# Sensor_shoot.net
KiCad netlist of a schematic drawn in Altium Designer
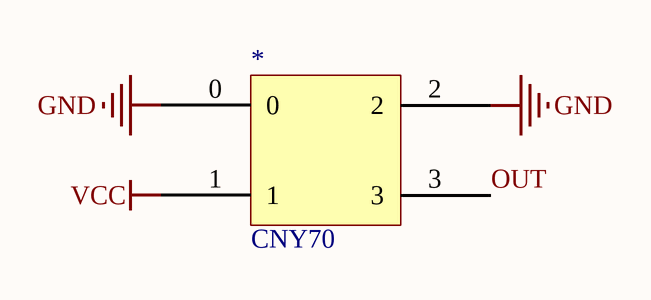
[diagram p0: Sensor shoot.SchDoc]

(export (version "E")
  (design (tool "Eeschema 10.0.6"))
  (components (comp (ref "*") (value "CNY70") (footprint "CNY70") (libsource (lib "KN2CLib") (part "CNY70"))))
  (nets
    (net (code "1") (name "/OUT") (class "Default")
      (node (ref "*") (pin "3") (pinfunction "3_3") (pintype "passive"))
    )
    (net (code "2") (name "GND") (class "Default")
      (node (ref "*") (pin "0") (pinfunction "0_0") (pintype "passive"))
      (node (ref "*") (pin "2") (pinfunction "2_2") (pintype "passive"))
    )
    (net (code "3") (name "VCC") (class "Default")
      (node (ref "*") (pin "1") (pinfunction "1_1") (pintype "passive"))
    )
  )
)
